# Sheet1.net
KiCad netlist of a schematic drawn in Altium Designer
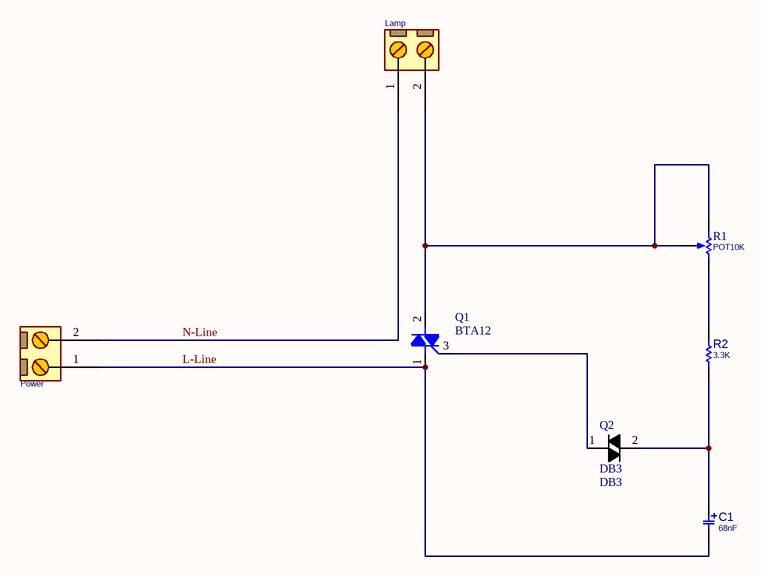
[diagram p0: Sheet1.SchDoc]

(export (version "E")
  (design (tool "Eeschema 10.0.6"))
  (components
    (comp (ref "C1")
      (value "68nF")
      (footprint "C_FLM_7X5H11")
      (description "CAP, THD, FILM,")
      (fields (field (name "MANF_P#") "MANF_PART#") (field (name "MANF") "MANF"))
      (libsource (lib "passive_thd") (part "CAP_THD_FLM"))
    )
    (comp (ref "Lamp")
      (value "CONN_TB2")
      (footprint "MSTB_2")
      (description "CONN, PHOENIX MSTB, 5-G, 5.08mm pitch")
      (libsource (lib "conn_terminalB") (part "CONN_MSTB_2"))
    )
    (comp (ref "Power")
      (value "CONN_TB2")
      (footprint "MSTB_2")
      (description "CONN, PHOENIX MSTB, 5-G, 5.08mm pitch")
      (libsource (lib "") (part "CONN_MSTB_2_1"))
    )
    (comp (ref "Q1")
      (value "BTA12")
      (footprint "TO220_3")
      (description "Triac, 600V, 12A, TO-220")
      (fields (field (name "MANF_P#") "BTA12-600BW, BTA12-600CW, BTA12-600TW") (field (name "MANF") "ST"))
      (libsource (lib "triac_diac") (part "TRIAC_BTA12-600_TO220"))
    )
    (comp (ref "Q2")
      (value "DB3")
      (footprint "D_AX03_DO35")
      (description "Diac, 32VBO, DO-35")
      (fields (field (name "MANF") "ST") (field (name "ALTIUM_VALUE") "DB3"))
      (libsource (lib "triac_diac") (part "DIAC_DB3_DO35"))
    )
    (comp (ref "R1")
      (value "POT10K")
      (footprint "VOL_R")
      (description "RESISTOR, THD, Potentiometer Volume")
      (libsource (lib "resistor_pot_trimmer") (part "RES_THD_POT_VOL"))
    )
    (comp (ref "R2")
      (value "3.3K")
      (footprint "R025W_AX04")
      (description "RESISTOR, THD")
      (fields (field (name "MANF_P#") "RK73H1ETTP4701F") (field (name "MANF") "KOA SPEER"))
      (libsource (lib "passive_thd") (part "RES_THD"))
    )
  )
  (nets
    (net (code "1") (name "/L-Line") (class "Default")
      (node (ref "C1") (pin "2") (pinfunction "2_2") (pintype "passive"))
      (node (ref "Power") (pin "1") (pinfunction "1_1") (pintype "passive"))
      (node (ref "Q1") (pin "1") (pinfunction "T1_1") (pintype "passive"))
    )
    (net (code "2") (name "/N-Line") (class "Default")
      (node (ref "Lamp") (pin "1") (pinfunction "1_1") (pintype "passive"))
      (node (ref "Power") (pin "2") (pinfunction "2_2") (pintype "passive"))
    )
    (net (code "3") (name "Net-(Q1-G)") (class "Default")
      (node (ref "Q1") (pin "3") (pinfunction "G_3") (pintype "passive"))
      (node (ref "Q2") (pin "1") (pinfunction "A1_1") (pintype "passive"))
    )
    (net (code "4") (name "Net-(Q1-T2)") (class "Default")
      (node (ref "Lamp") (pin "2") (pinfunction "2_2") (pintype "passive"))
      (node (ref "Q1") (pin "2") (pinfunction "T2_2") (pintype "passive"))
      (node (ref "R1") (pin "1") (pinfunction "TOP_1") (pintype "passive"))
      (node (ref "R1") (pin "2") (pinfunction "TAP_2") (pintype "passive"))
    )
    (net (code "5") (name "Net-(Q2-A2)") (class "Default")
      (node (ref "C1") (pin "1") (pinfunction "1_1") (pintype "passive"))
      (node (ref "Q2") (pin "2") (pinfunction "A2_2") (pintype "passive"))
      (node (ref "R2") (pin "1") (pinfunction "1_1") (pintype "passive"))
    )
    (net (code "6") (name "Net-(R1-BOT)") (class "Default")
      (node (ref "R1") (pin "3") (pinfunction "BOT_3") (pintype "passive"))
      (node (ref "R2") (pin "2") (pinfunction "2_2") (pintype "passive"))
    )
  )
)
